# Display_Pics.net
KiCad netlist of a schematic drawn in EAGLE
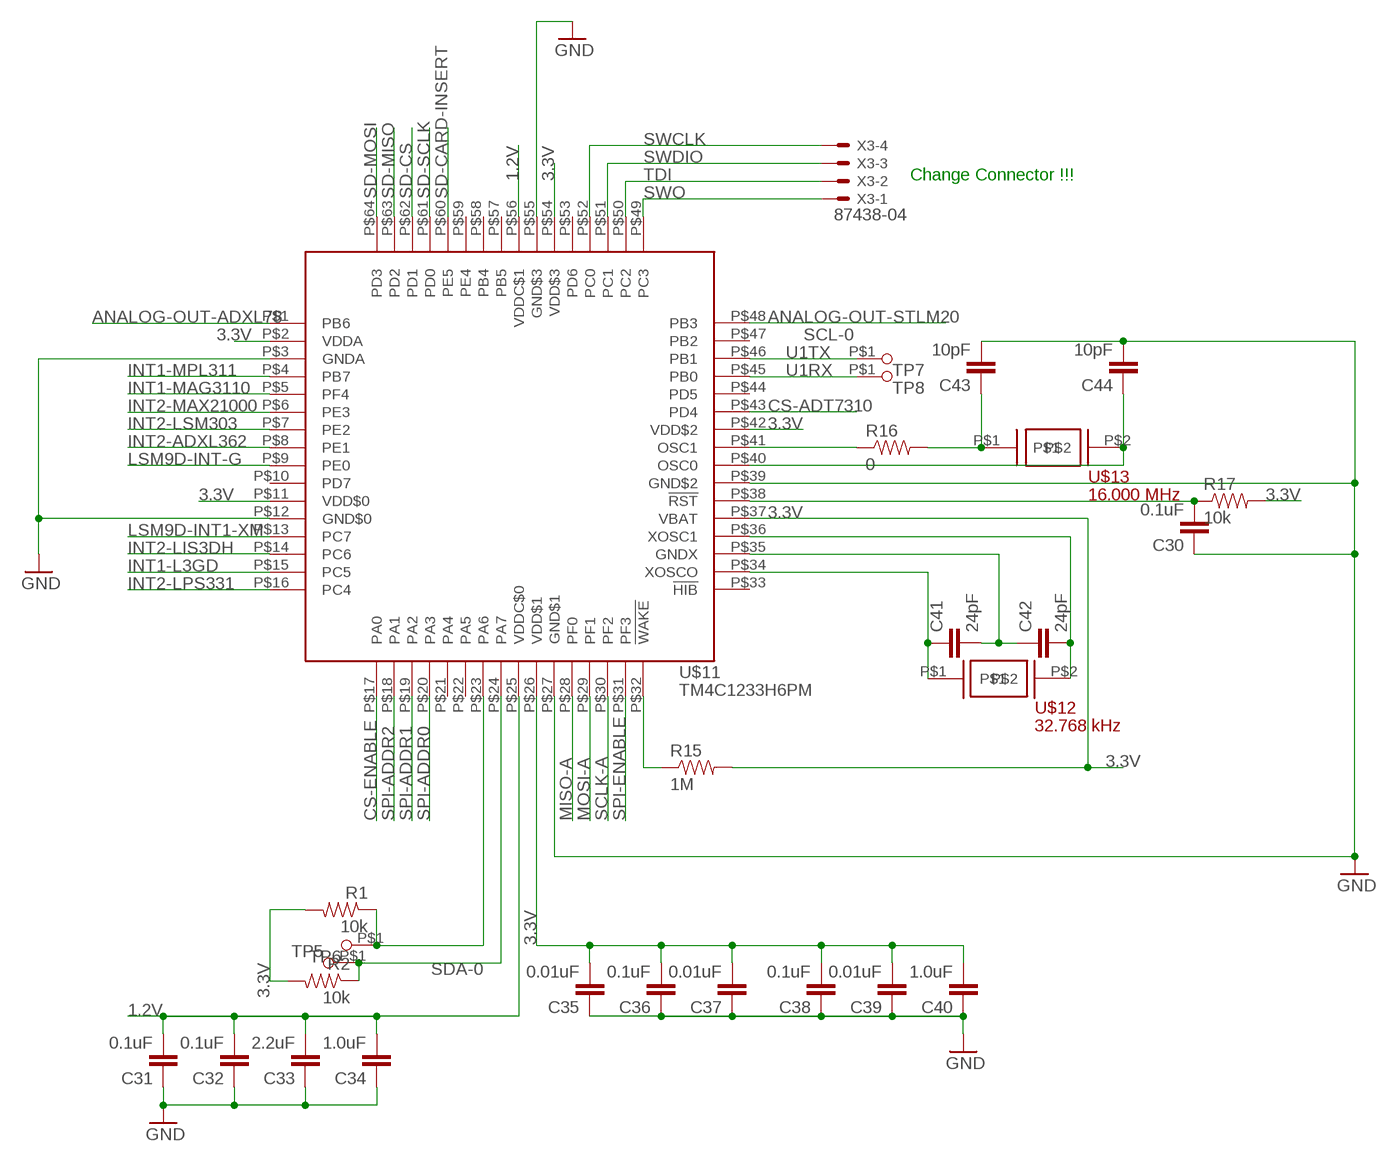
[diagram p0: schematic, sheet 1]
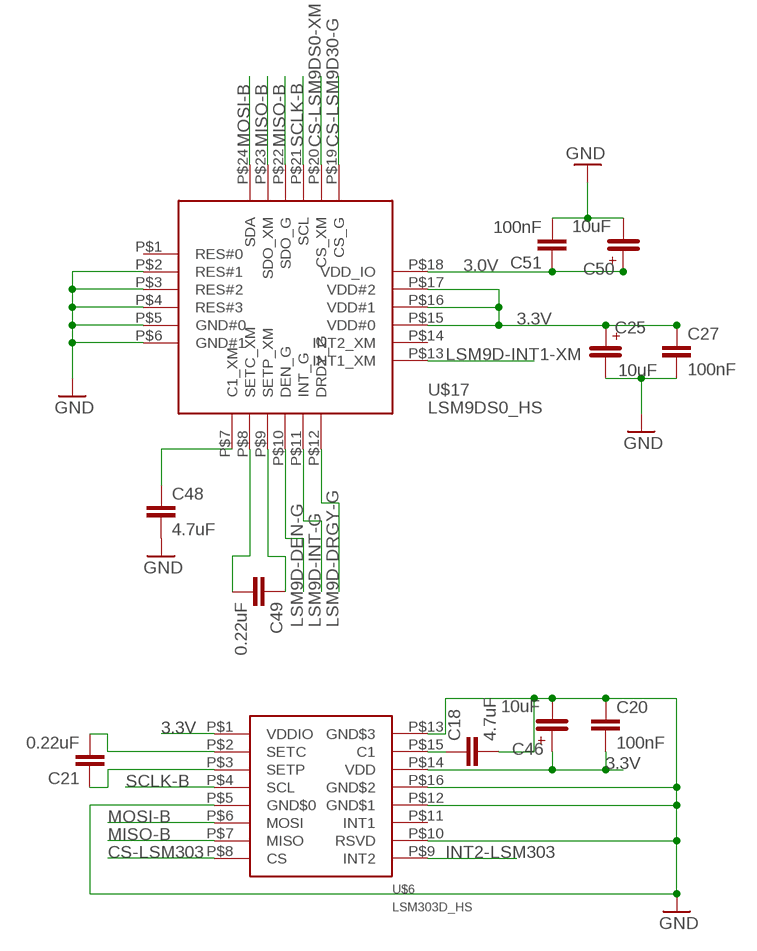
[diagram p1: schematic, sheet 2]
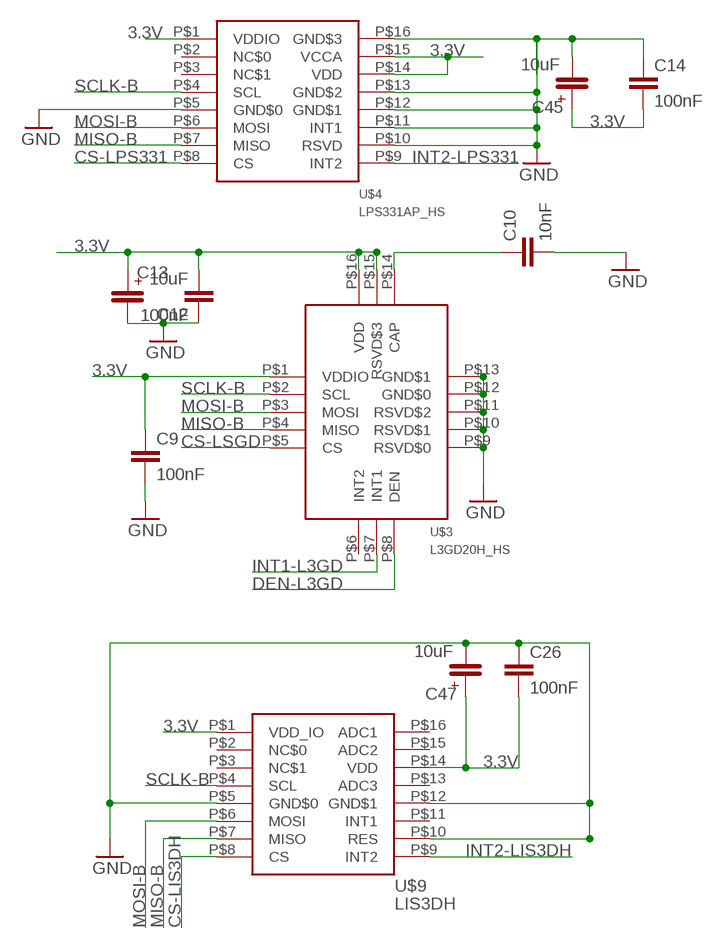
[diagram p2: schematic, sheet 3]
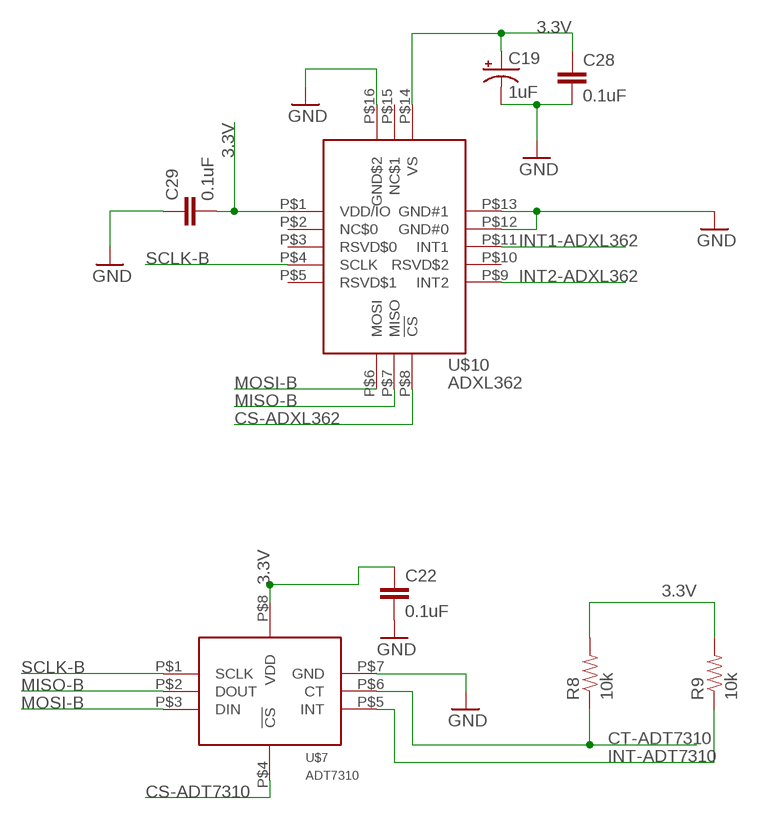
[diagram p3: schematic, sheet 4]
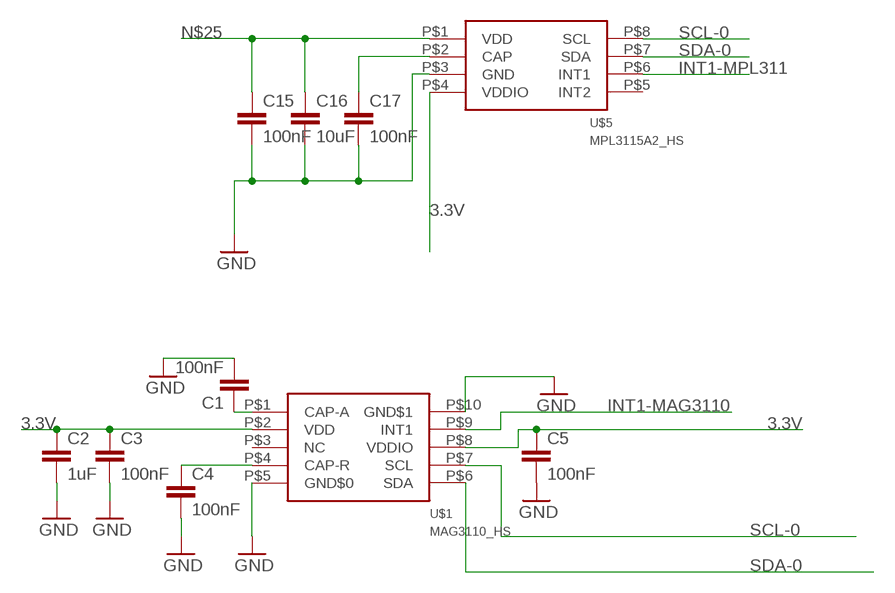
[diagram p4: schematic, sheet 5]
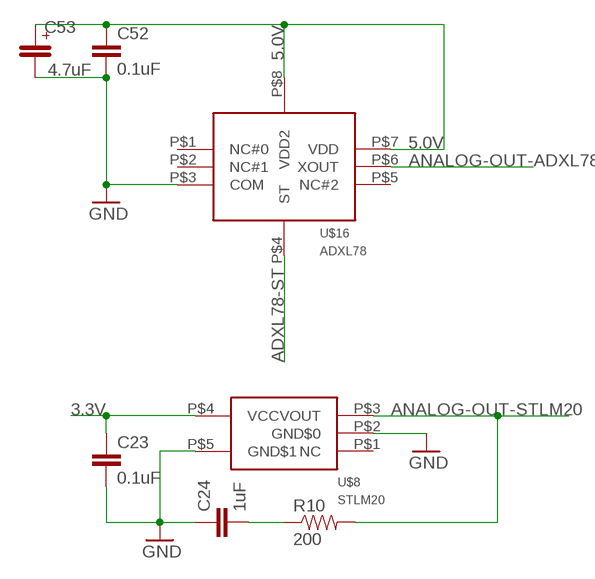
[diagram p5: schematic, sheet 6]
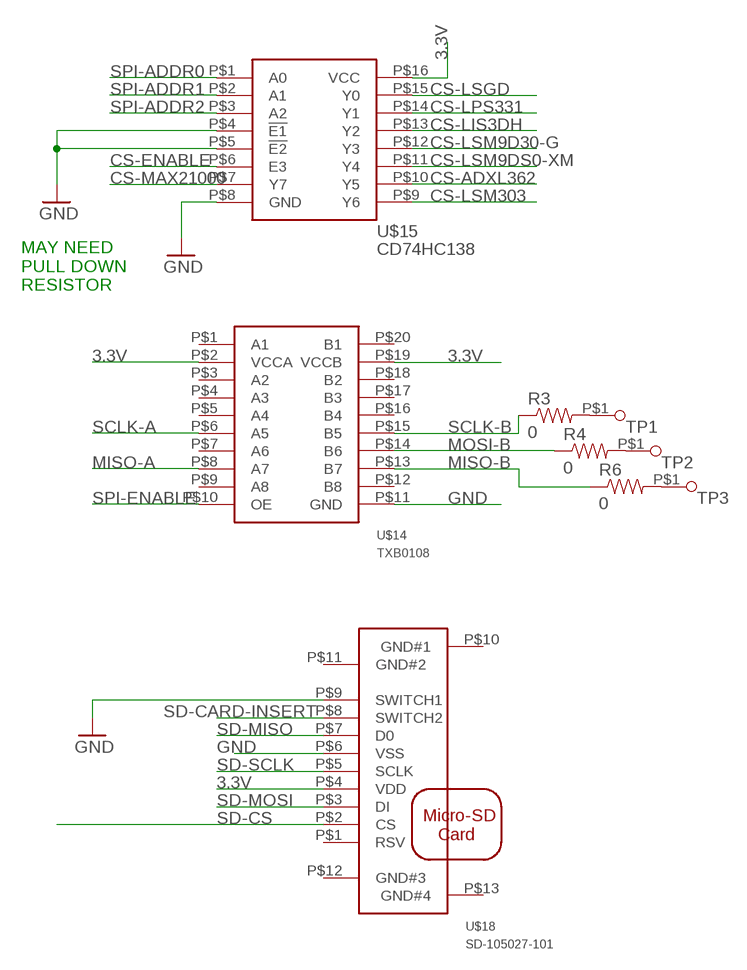
[diagram p6: schematic, sheet 7]
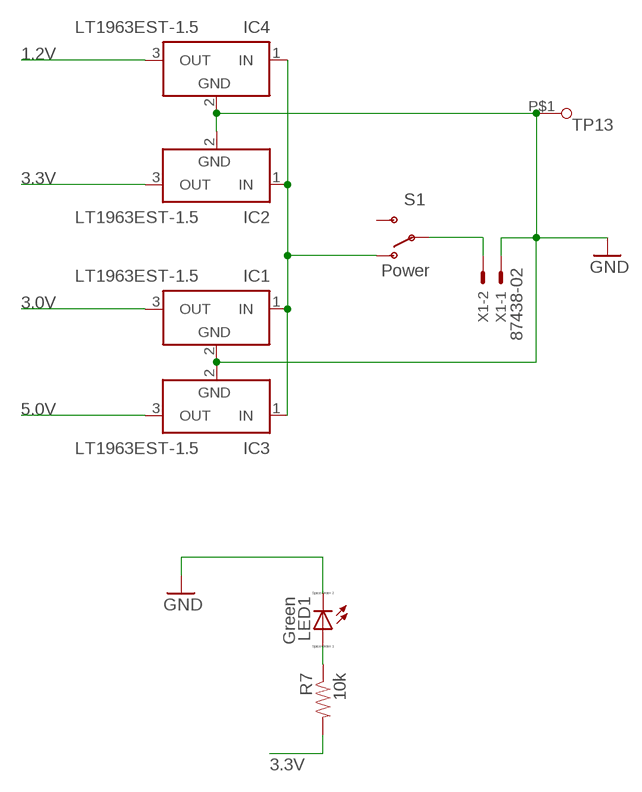
[diagram p7: schematic, sheet 8]
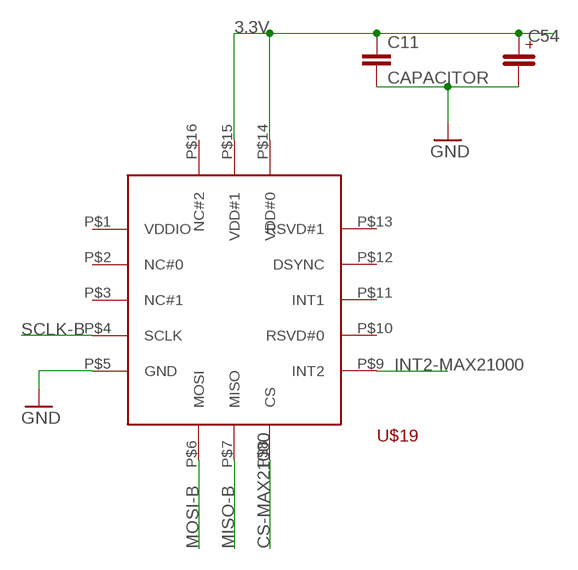
[diagram p8: schematic, sheet 9]

(export (version "E")
  (design (tool "Eeschema 10.0.6"))
  (components
    (comp (ref "C9")
      (value "100nF")
      (footprint "eagle-import:0402-CAP")
      (libsource (lib "eagle-import") (part "CAPACITOR"))
    )
    (comp (ref "C10")
      (value "10nF")
      (footprint "eagle-import:0402-CAP")
      (libsource (lib "eagle-import") (part "CAPACITOR"))
    )
    (comp (ref "C12")
      (value "10uF")
      (footprint "eagle-import:0402-CAP")
      (libsource (lib "eagle-import") (part "CAPACITOR"))
    )
    (comp (ref "C13")
      (value "100nF")
      (footprint "eagle-import:4.3X7.3SMD")
      (libsource (lib "eagle-import") (part "EEFCD0J100ER"))
    )
    (comp (ref "C14")
      (value "100nF")
      (footprint "eagle-import:0402-CAP")
      (libsource (lib "eagle-import") (part "CAPACITOR"))
    )
    (comp (ref "C26")
      (value "100nF")
      (footprint "eagle-import:0402-CAP")
      (libsource (lib "eagle-import") (part "CAPACITOR"))
    )
    (comp (ref "C45")
      (value "10uF")
      (footprint "eagle-import:4.3X7.3SMD")
      (libsource (lib "eagle-import") (part "EEFCD0J100ER"))
    )
    (comp (ref "C47")
      (value "10uF")
      (footprint "eagle-import:4.3X7.3SMD")
      (libsource (lib "eagle-import") (part "EEFCD0J100ER"))
    )
    (comp (ref "U$3")
      (value "L3GD20H_HS")
      (footprint "eagle-import:LGA-16(3X3)_HS")
      (libsource (lib "eagle-import") (part "L3GD20H_HS"))
    )
    (comp (ref "U$4")
      (value "LPS331AP_HS")
      (footprint "eagle-import:LGA-16(3X3)_HS")
      (libsource (lib "eagle-import") (part "LPS331AP_HS"))
    )
    (comp (ref "U$9")
      (value "LIS3DH")
      (footprint "eagle-import:LGA-16(3X3)_HS")
      (libsource (lib "eagle-import") (part "LIS3DH_HS"))
    )
    (comp (ref "C30")
      (value "0.1uF")
      (footprint "eagle-import:0402-CAP")
      (libsource (lib "eagle-import") (part "CAPACITOR"))
    )
    (comp (ref "C31")
      (value "0.1uF")
      (footprint "eagle-import:0402-CAP")
      (libsource (lib "eagle-import") (part "CAPACITOR"))
    )
    (comp (ref "C32")
      (value "0.1uF")
      (footprint "eagle-import:0402-CAP")
      (libsource (lib "eagle-import") (part "CAPACITOR"))
    )
    (comp (ref "C33")
      (value "2.2uF")
      (footprint "eagle-import:0402-CAP")
      (libsource (lib "eagle-import") (part "CAPACITOR"))
    )
    (comp (ref "C34")
      (value "1.0uF")
      (footprint "eagle-import:0402-CAP")
      (libsource (lib "eagle-import") (part "CAPACITOR"))
    )
    (comp (ref "C35")
      (value "0.01uF")
      (footprint "eagle-import:0402-CAP")
      (libsource (lib "eagle-import") (part "CAPACITOR"))
    )
    (comp (ref "C36")
      (value "0.1uF")
      (footprint "eagle-import:0402-CAP")
      (libsource (lib "eagle-import") (part "CAPACITOR"))
    )
    (comp (ref "C37")
      (value "0.01uF")
      (footprint "eagle-import:0402-CAP")
      (libsource (lib "eagle-import") (part "CAPACITOR"))
    )
    (comp (ref "C38")
      (value "0.1uF")
      (footprint "eagle-import:0402-CAP")
      (libsource (lib "eagle-import") (part "CAPACITOR"))
    )
    (comp (ref "C39")
      (value "0.01uF")
      (footprint "eagle-import:0402-CAP")
      (libsource (lib "eagle-import") (part "CAPACITOR"))
    )
    (comp (ref "C40")
      (value "1.0uF")
      (footprint "eagle-import:0402-CAP")
      (libsource (lib "eagle-import") (part "CAPACITOR"))
    )
    (comp (ref "C41")
      (value "24pF")
      (footprint "eagle-import:0402-CAP")
      (libsource (lib "eagle-import") (part "CAPACITOR"))
    )
    (comp (ref "C42")
      (value "24pF")
      (footprint "eagle-import:0402-CAP")
      (libsource (lib "eagle-import") (part "CAPACITOR"))
    )
    (comp (ref "C43")
      (value "10pF")
      (footprint "eagle-import:0402-CAP")
      (libsource (lib "eagle-import") (part "CAPACITOR"))
    )
    (comp (ref "C44")
      (value "10pF")
      (footprint "eagle-import:0402-CAP")
      (libsource (lib "eagle-import") (part "CAPACITOR"))
    )
    (comp (ref "R1")
      (value "10k")
      (footprint "eagle-import:0402-RES")
      (libsource (lib "eagle-import") (part "RESISTOR"))
    )
    (comp (ref "R2")
      (value "10k")
      (footprint "eagle-import:0402-RES")
      (libsource (lib "eagle-import") (part "RESISTOR"))
    )
    (comp (ref "R15")
      (value "1M")
      (footprint "eagle-import:0402-RES")
      (libsource (lib "eagle-import") (part "RESISTOR"))
    )
    (comp (ref "R16")
      (value "0")
      (footprint "eagle-import:0402-RES")
      (libsource (lib "eagle-import") (part "RESISTOR"))
    )
    (comp (ref "R17")
      (value "10k")
      (footprint "eagle-import:0402-RES")
      (libsource (lib "eagle-import") (part "RESISTOR"))
    )
    (comp (ref "TP5")
      (value "TESTPAD(ROUND)")
      (footprint "eagle-import:TESTPAD(ROUND)")
      (libsource (lib "eagle-import") (part "TESTPAD(ROUND)"))
    )
    (comp (ref "TP6")
      (value "TESTPAD(ROUND)")
      (footprint "eagle-import:TESTPAD(ROUND)")
      (libsource (lib "eagle-import") (part "TESTPAD(ROUND)"))
    )
    (comp (ref "TP7")
      (value "TESTPAD(ROUND)")
      (footprint "eagle-import:TESTPAD(ROUND)")
      (libsource (lib "eagle-import") (part "TESTPAD(ROUND)"))
    )
    (comp (ref "TP8")
      (value "TESTPAD(ROUND)")
      (footprint "eagle-import:TESTPAD(ROUND)")
      (libsource (lib "eagle-import") (part "TESTPAD(ROUND)"))
    )
    (comp (ref "U$11")
      (value "TM4C1233H6PM")
      (footprint "eagle-import:S-PQFP-G64")
      (libsource (lib "eagle-import") (part "TM4C1233H6PM"))
    )
    (comp (ref "U$12")
      (value "32.768 kHz")
      (footprint "eagle-import:CYLINDRICAL-(1.9DIAX6L)")
      (libsource (lib "eagle-import") (part "AB26TRB"))
    )
    (comp (ref "U$13")
      (value "16.000 MHz")
      (footprint "eagle-import:2-SMD")
      (libsource (lib "eagle-import") (part "NX5032GA"))
    )
    (comp (ref "X3")
      (value "87438-04")
      (footprint "eagle-import:87438-04")
      (libsource (lib "eagle-import") (part "87438-04"))
    )
    (comp (ref "C18")
      (value "4.7uF")
      (footprint "eagle-import:0402-CAP")
      (libsource (lib "eagle-import") (part "CAPACITOR"))
    )
    (comp (ref "C20")
      (value "100nF")
      (footprint "eagle-import:0402-CAP")
      (libsource (lib "eagle-import") (part "CAPACITOR"))
    )
    (comp (ref "C21")
      (value "0.22uF")
      (footprint "eagle-import:0402-CAP")
      (libsource (lib "eagle-import") (part "CAPACITOR"))
    )
    (comp (ref "C25")
      (value "10uF")
      (footprint "eagle-import:4.3X7.3SMD")
      (libsource (lib "eagle-import") (part "EEFCD0J100ER"))
    )
    (comp (ref "C27")
      (value "100nF")
      (footprint "eagle-import:0402-CAP")
      (libsource (lib "eagle-import") (part "CAPACITOR"))
    )
    (comp (ref "C46")
      (value "10uF")
      (footprint "eagle-import:4.3X7.3SMD")
      (libsource (lib "eagle-import") (part "EEFCD0J100ER"))
    )
    (comp (ref "C48")
      (value "4.7uF")
      (footprint "eagle-import:0402-CAP")
      (libsource (lib "eagle-import") (part "CAPACITOR"))
    )
    (comp (ref "C49")
      (value "0.22uF")
      (footprint "eagle-import:0402-CAP")
      (libsource (lib "eagle-import") (part "CAPACITOR"))
    )
    (comp (ref "C50")
      (value "10uF")
      (footprint "eagle-import:4.3X7.3SMD")
      (libsource (lib "eagle-import") (part "EEFCD0J100ER"))
    )
    (comp (ref "C51")
      (value "100nF")
      (footprint "eagle-import:0402-CAP")
      (libsource (lib "eagle-import") (part "CAPACITOR"))
    )
    (comp (ref "U$6")
      (value "LSM303D_HS")
      (footprint "eagle-import:LGA-16(3X3)_HS")
      (libsource (lib "eagle-import") (part "LSM303D_HS"))
    )
    (comp (ref "U$17")
      (value "LSM9DS0_HS")
      (footprint "eagle-import:LGA-24(4X4)_HS")
      (libsource (lib "eagle-import") (part "LSM9DS0_HS"))
    )
    (comp (ref "C23")
      (value "0.1uF")
      (footprint "eagle-import:0402-CAP")
      (libsource (lib "eagle-import") (part "CAPACITOR"))
    )
    (comp (ref "C24")
      (value "1uF")
      (footprint "eagle-import:0402-CAP")
      (libsource (lib "eagle-import") (part "CAPACITOR"))
    )
    (comp (ref "C52")
      (value "0.1uF")
      (footprint "eagle-import:0402-CAP")
      (libsource (lib "eagle-import") (part "CAPACITOR"))
    )
    (comp (ref "C53")
      (value "4.7uF")
      (footprint "eagle-import:4.3X7.3SMD")
      (libsource (lib "eagle-import") (part "EEFCD0J100ER"))
    )
    (comp (ref "R10")
      (value "200")
      (footprint "eagle-import:0402-RES")
      (libsource (lib "eagle-import") (part "RESISTOR"))
    )
    (comp (ref "U$8")
      (value "STLM20")
      (footprint "eagle-import:SOT323-5L")
      (libsource (lib "eagle-import") (part "STLM20"))
    )
    (comp (ref "U$16")
      (value "ADXL78")
      (footprint "eagle-import:LCC-8(5X5)_HS")
      (libsource (lib "eagle-import") (part "ADXL78"))
    )
    (comp (ref "IC1")
      (value "LT1963EST-1.5")
      (footprint "eagle-import:SOT223")
      (libsource (lib "eagle-import") (part "LT1963EST-1.5"))
    )
    (comp (ref "IC2")
      (value "LT1963EST-1.5")
      (footprint "eagle-import:SOT223")
      (libsource (lib "eagle-import") (part "LT1963EST-1.5"))
    )
    (comp (ref "IC3")
      (value "LT1963EST-1.5")
      (footprint "eagle-import:SOT223")
      (libsource (lib "eagle-import") (part "LT1963EST-1.5"))
    )
    (comp (ref "IC4")
      (value "LT1963EST-1.5")
      (footprint "eagle-import:SOT223")
      (libsource (lib "eagle-import") (part "LT1963EST-1.5"))
    )
    (comp (ref "LED1")
      (value "Green")
      (footprint "eagle-import:LED_SML0603")
      (libsource (lib "eagle-import") (part "LED_ESML0603"))
    )
    (comp (ref "R7")
      (value "10k")
      (footprint "eagle-import:0402-RES")
      (libsource (lib "eagle-import") (part "RESISTOR"))
    )
    (comp (ref "S1")
      (value "Power")
      (footprint "eagle-import:SWITCH-SPST-SMD-A")
      (libsource (lib "eagle-import") (part "SWITCH-SPDT-SMD-A"))
    )
    (comp (ref "TP13")
      (value "TESTPAD(ROUND)")
      (footprint "eagle-import:TESTPAD(ROUND)")
      (libsource (lib "eagle-import") (part "TESTPAD(ROUND)"))
    )
    (comp (ref "X1")
      (value "87438-02")
      (footprint "eagle-import:87438-02")
      (libsource (lib "eagle-import") (part "87438-02"))
    )
    (comp (ref "C1")
      (value "100nF")
      (footprint "eagle-import:0402-CAP")
      (libsource (lib "eagle-import") (part "CAPACITOR"))
    )
    (comp (ref "C2")
      (value "1uF")
      (footprint "eagle-import:0402-CAP")
      (libsource (lib "eagle-import") (part "CAPACITOR"))
    )
    (comp (ref "C3")
      (value "100nF")
      (footprint "eagle-import:0402-CAP")
      (libsource (lib "eagle-import") (part "CAPACITOR"))
    )
    (comp (ref "C4")
      (value "100nF")
      (footprint "eagle-import:0402-CAP")
      (libsource (lib "eagle-import") (part "CAPACITOR"))
    )
    (comp (ref "C5")
      (value "100nF")
      (footprint "eagle-import:0402-CAP")
      (libsource (lib "eagle-import") (part "CAPACITOR"))
    )
    (comp (ref "C15")
      (value "100nF")
      (footprint "eagle-import:0402-CAP")
      (libsource (lib "eagle-import") (part "CAPACITOR"))
    )
    (comp (ref "C16")
      (value "10uF")
      (footprint "eagle-import:0402-CAP")
      (libsource (lib "eagle-import") (part "CAPACITOR"))
    )
    (comp (ref "C17")
      (value "100nF")
      (footprint "eagle-import:0402-CAP")
      (libsource (lib "eagle-import") (part "CAPACITOR"))
    )
    (comp (ref "U$1")
      (value "MAG3110_HS")
      (footprint "eagle-import:DFN-10(2X2)_HS")
      (libsource (lib "eagle-import") (part "MAG3110_HS"))
    )
    (comp (ref "U$5")
      (value "MPL3115A2_HS")
      (footprint "eagle-import:LGA-8(5X3)_HS")
      (libsource (lib "eagle-import") (part "MPL3115A2_HS"))
    )
    (comp (ref "R3")
      (value "0")
      (footprint "eagle-import:0402-RES")
      (libsource (lib "eagle-import") (part "RESISTOR"))
    )
    (comp (ref "R4")
      (value "0")
      (footprint "eagle-import:0402-RES")
      (libsource (lib "eagle-import") (part "RESISTOR"))
    )
    (comp (ref "R6")
      (value "0")
      (footprint "eagle-import:0402-RES")
      (libsource (lib "eagle-import") (part "RESISTOR"))
    )
    (comp (ref "TP1")
      (value "TESTPAD(ROUND)")
      (footprint "eagle-import:TESTPAD(ROUND)")
      (libsource (lib "eagle-import") (part "TESTPAD(ROUND)"))
    )
    (comp (ref "TP2")
      (value "TESTPAD(ROUND)")
      (footprint "eagle-import:TESTPAD(ROUND)")
      (libsource (lib "eagle-import") (part "TESTPAD(ROUND)"))
    )
    (comp (ref "TP3")
      (value "TESTPAD(ROUND)")
      (footprint "eagle-import:TESTPAD(ROUND)")
      (libsource (lib "eagle-import") (part "TESTPAD(ROUND)"))
    )
    (comp (ref "U$14")
      (value "TXB0108")
      (footprint "eagle-import:TSSOP-(PW)-20")
      (libsource (lib "eagle-import") (part "TXB0108"))
    )
    (comp (ref "U$15")
      (value "CD74HC138")
      (footprint "eagle-import:SOIC-16")
      (libsource (lib "eagle-import") (part "CD74HC138"))
    )
    (comp (ref "U$18")
      (value "SD-105027-101")
      (footprint "eagle-import:SD-105027-101")
      (libsource (lib "eagle-import") (part "SD-105027-101"))
    )
    (comp (ref "C19")
      (value "1uF")
      (footprint "eagle-import:EIA6032")
      (libsource (lib "eagle-import") (part "CAP_POL6032"))
    )
    (comp (ref "C22")
      (value "0.1uF")
      (footprint "eagle-import:0402-CAP")
      (libsource (lib "eagle-import") (part "CAPACITOR"))
    )
    (comp (ref "C28")
      (value "0.1uF")
      (footprint "eagle-import:0402-CAP")
      (libsource (lib "eagle-import") (part "CAPACITOR"))
    )
    (comp (ref "C29")
      (value "0.1uF")
      (footprint "eagle-import:0402-CAP")
      (libsource (lib "eagle-import") (part "CAPACITOR"))
    )
    (comp (ref "R8")
      (value "10k")
      (footprint "eagle-import:0402-RES")
      (libsource (lib "eagle-import") (part "RESISTOR"))
    )
    (comp (ref "R9")
      (value "10k")
      (footprint "eagle-import:0402-RES")
      (libsource (lib "eagle-import") (part "RESISTOR"))
    )
    (comp (ref "U$7")
      (value "ADT7310")
      (footprint "eagle-import:SOIC-8(5X6.2)")
      (libsource (lib "eagle-import") (part "ADT7310"))
    )
    (comp (ref "U$10")
      (value "ADXL362")
      (footprint "eagle-import:LGA-16(3X3.25)_HS")
      (libsource (lib "eagle-import") (part "ADXL362_HS"))
    )
    (comp (ref "C11")
      (value "CAPACITOR")
      (footprint "eagle-import:0402-CAP")
      (libsource (lib "eagle-import") (part "CAPACITOR"))
    )
    (comp (ref "C54")
      (value "EEFCD0J100ER")
      (footprint "eagle-import:4.3X7.3SMD")
      (libsource (lib "eagle-import") (part "EEFCD0J100ER"))
    )
    (comp (ref "U$19")
      (value "MAX21000_HS")
      (footprint "eagle-import:LGA-16(3X3)_HS")
      (libsource (lib "eagle-import") (part "MAX21000_HS"))
    )
  )
  (nets
    (net (code "1") (name "1.2V") (class "Default")
      (node (ref "C31") (pin "2") (pinfunction "2_2") (pintype "passive"))
      (node (ref "C32") (pin "2") (pinfunction "2_2") (pintype "passive"))
      (node (ref "C33") (pin "2") (pinfunction "2_2") (pintype "passive"))
      (node (ref "C34") (pin "2") (pinfunction "2_2") (pintype "passive"))
      (node (ref "IC4") (pin "3") (pinfunction "OUT_3") (pintype "output"))
      (node (ref "U$11") (pin "P$25") (pinfunction "VDDC$0_P$25") (pintype "bidirectional"))
      (node (ref "U$11") (pin "P$56") (pinfunction "VDDC$1_P$56") (pintype "bidirectional"))
    )
    (net (code "2") (name "3.0V") (class "Default")
      (node (ref "C50") (pin "P$1") (pintype "bidirectional"))
      (node (ref "C51") (pin "1") (pinfunction "1_1") (pintype "passive"))
      (node (ref "IC1") (pin "3") (pinfunction "OUT_3") (pintype "output"))
      (node (ref "U$17") (pin "P$18") (pinfunction "VDD_IO_P$18") (pintype "bidirectional"))
    )
    (net (code "3") (name "3.3V") (class "Default")
      (node (ref "C11") (pin "1") (pinfunction "1_1") (pintype "passive"))
      (node (ref "C12") (pin "2") (pinfunction "2_2") (pintype "passive"))
      (node (ref "C13") (pin "P$1") (pintype "bidirectional"))
      (node (ref "C14") (pin "2") (pinfunction "2_2") (pintype "passive"))
      (node (ref "C19") (pin "P$1") (pinfunction "+_P$1") (pintype "passive"))
      (node (ref "C2") (pin "1") (pinfunction "1_1") (pintype "passive"))
      (node (ref "C20") (pin "2") (pinfunction "2_2") (pintype "passive"))
      (node (ref "C22") (pin "1") (pinfunction "1_1") (pintype "passive"))
      (node (ref "C23") (pin "1") (pinfunction "1_1") (pintype "passive"))
      (node (ref "C25") (pin "P$1") (pintype "bidirectional"))
      (node (ref "C26") (pin "2") (pinfunction "2_2") (pintype "passive"))
      (node (ref "C27") (pin "1") (pinfunction "1_1") (pintype "passive"))
      (node (ref "C28") (pin "1") (pinfunction "1_1") (pintype "passive"))
      (node (ref "C29") (pin "2") (pinfunction "2_2") (pintype "passive"))
      (node (ref "C3") (pin "1") (pinfunction "1_1") (pintype "passive"))
      (node (ref "C35") (pin "2") (pinfunction "2_2") (pintype "passive"))
      (node (ref "C36") (pin "2") (pinfunction "2_2") (pintype "passive"))
      (node (ref "C37") (pin "2") (pinfunction "2_2") (pintype "passive"))
      (node (ref "C38") (pin "2") (pinfunction "2_2") (pintype "passive"))
      (node (ref "C39") (pin "2") (pinfunction "2_2") (pintype "passive"))
      (node (ref "C40") (pin "2") (pinfunction "2_2") (pintype "passive"))
      (node (ref "C45") (pin "P$1") (pintype "bidirectional"))
      (node (ref "C46") (pin "P$1") (pintype "bidirectional"))
      (node (ref "C47") (pin "P$1") (pintype "bidirectional"))
      (node (ref "C5") (pin "1") (pinfunction "1_1") (pintype "passive"))
      (node (ref "C54") (pin "P$1") (pintype "bidirectional"))
      (node (ref "C9") (pin "1") (pinfunction "1_1") (pintype "passive"))
      (node (ref "IC2") (pin "3") (pinfunction "OUT_3") (pintype "output"))
      (node (ref "R1") (pin "2") (pinfunction "2_2") (pintype "passive"))
      (node (ref "R15") (pin "2") (pinfunction "2_2") (pintype "passive"))
      (node (ref "R17") (pin "2") (pinfunction "2_2") (pintype "passive"))
      (node (ref "R2") (pin "2") (pinfunction "2_2") (pintype "passive"))
      (node (ref "R7") (pin "2") (pinfunction "2_2") (pintype "passive"))
      (node (ref "R8") (pin "2") (pinfunction "2_2") (pintype "passive"))
      (node (ref "R9") (pin "2") (pinfunction "2_2") (pintype "passive"))
      (node (ref "U$1") (pin "P$2") (pinfunction "VDD_P$2") (pintype "bidirectional"))
      (node (ref "U$1") (pin "P$8") (pinfunction "VDDIO_P$8") (pintype "bidirectional"))
      (node (ref "U$10") (pin "P$1") (pinfunction "VDD/IO_P$1") (pintype "bidirectional"))
      (node (ref "U$10") (pin "P$14") (pinfunction "VS_P$14") (pintype "bidirectional"))
      (node (ref "U$11") (pin "P$11") (pinfunction "VDD$0_P$11") (pintype "bidirectional"))
      (node (ref "U$11") (pin "P$2") (pinfunction "VDDA_P$2") (pintype "bidirectional"))
      (node (ref "U$11") (pin "P$26") (pinfunction "VDD$1_P$26") (pintype "bidirectional"))
      (node (ref "U$11") (pin "P$37") (pinfunction "VBAT_P$37") (pintype "bidirectional"))
      (node (ref "U$11") (pin "P$42") (pinfunction "VDD$2_P$42") (pintype "bidirectional"))
      (node (ref "U$11") (pin "P$54") (pinfunction "VDD$3_P$54") (pintype "bidirectional"))
      (node (ref "U$14") (pin "P$19") (pinfunction "VCCB_P$19") (pintype "bidirectional"))
      (node (ref "U$14") (pin "P$2") (pinfunction "VCCA_P$2") (pintype "bidirectional"))
      (node (ref "U$15") (pin "P$16") (pinfunction "VCC_P$16") (pintype "bidirectional"))
      (node (ref "U$17") (pin "P$15") (pinfunction "VDD#0_P$15") (pintype "bidirectional"))
      (node (ref "U$17") (pin "P$16") (pinfunction "VDD#1_P$16") (pintype "bidirectional"))
      (node (ref "U$17") (pin "P$17") (pinfunction "VDD#2_P$17") (pintype "bidirectional"))
      (node (ref "U$18") (pin "P$4") (pinfunction "VDD_P$4") (pintype "bidirectional"))
      (node (ref "U$19") (pin "P$14") (pinfunction "VDD#0_P$14") (pintype "bidirectional"))
      (node (ref "U$19") (pin "P$15") (pinfunction "VDD#1_P$15") (pintype "bidirectional"))
      (node (ref "U$3") (pin "P$1") (pinfunction "VDDIO_P$1") (pintype "bidirectional"))
      (node (ref "U$3") (pin "P$15") (pinfunction "RSVD$3_P$15") (pintype "bidirectional"))
      (node (ref "U$3") (pin "P$16") (pinfunction "VDD_P$16") (pintype "bidirectional"))
      (node (ref "U$4") (pin "P$1") (pinfunction "VDDIO_P$1") (pintype "bidirectional"))
      (node (ref "U$4") (pin "P$14") (pinfunction "VDD_P$14") (pintype "bidirectional"))
      (node (ref "U$4") (pin "P$15") (pinfunction "VCCA_P$15") (pintype "bidirectional"))
      (node (ref "U$5") (pin "P$4") (pinfunction "VDDIO_P$4") (pintype "bidirectional"))
      (node (ref "U$6") (pin "P$1") (pinfunction "VDDIO_P$1") (pintype "bidirectional"))
      (node (ref "U$6") (pin "P$14") (pinfunction "VDD_P$14") (pintype "bidirectional"))
      (node (ref "U$7") (pin "P$8") (pinfunction "VDD_P$8") (pintype "bidirectional"))
      (node (ref "U$8") (pin "P$4") (pinfunction "VCC_P$4") (pintype "bidirectional"))
      (node (ref "U$9") (pin "P$1") (pinfunction "VDD_IO_P$1") (pintype "bidirectional"))
      (node (ref "U$9") (pin "P$14") (pinfunction "VDD_P$14") (pintype "bidirectional"))
    )
    (net (code "4") (name "5.0V") (class "Default")
      (node (ref "C52") (pin "1") (pinfunction "1_1") (pintype "passive"))
      (node (ref "C53") (pin "P$1") (pintype "bidirectional"))
      (node (ref "IC3") (pin "3") (pinfunction "OUT_3") (pintype "output"))
      (node (ref "U$16") (pin "P$7") (pinfunction "VDD_P$7") (pintype "bidirectional"))
      (node (ref "U$16") (pin "P$8") (pinfunction "VDD2_P$8") (pintype "bidirectional"))
    )
    (net (code "5") (name "ADXL78-ST") (class "Default")
      (node (ref "U$16") (pin "P$4") (pinfunction "ST_P$4") (pintype "bidirectional"))
    )
    (net (code "6") (name "ANALOG-OUT-ADXL78") (class "Default")
      (node (ref "U$11") (pin "P$1") (pinfunction "PB6_P$1") (pintype "bidirectional"))
      (node (ref "U$16") (pin "P$6") (pinfunction "XOUT_P$6") (pintype "bidirectional"))
    )
    (net (code "7") (name "ANALOG-OUT-STLM20") (class "Default")
      (node (ref "R10") (pin "2") (pinfunction "2_2") (pintype "passive"))
      (node (ref "U$11") (pin "P$48") (pinfunction "PB3_P$48") (pintype "bidirectional"))
      (node (ref "U$8") (pin "P$3") (pinfunction "VOUT_P$3") (pintype "bidirectional"))
    )
    (net (code "8") (name "CS-ADT7310") (class "Default")
      (node (ref "U$11") (pin "P$43") (pinfunction "PD4_P$43") (pintype "bidirectional"))
      (node (ref "U$7") (pin "P$4") (pinfunction "~{CS}_P$4") (pintype "bidirectional"))
    )
    (net (code "9") (name "CS-ADXL362") (class "Default")
      (node (ref "U$10") (pin "P$8") (pinfunction "~{CS}_P$8") (pintype "bidirectional"))
      (node (ref "U$15") (pin "P$10") (pinfunction "Y5_P$10") (pintype "bidirectional"))
    )
    (net (code "10") (name "CS-ENABLE") (class "Default")
      (node (ref "U$11") (pin "P$17") (pinfunction "PA0_P$17") (pintype "bidirectional"))
      (node (ref "U$15") (pin "P$6") (pinfunction "E3_P$6") (pintype "bidirectional"))
    )
    (net (code "11") (name "CS-LIS3DH") (class "Default")
      (node (ref "U$15") (pin "P$13") (pinfunction "Y2_P$13") (pintype "bidirectional"))
      (node (ref "U$9") (pin "P$8") (pinfunction "CS_P$8") (pintype "bidirectional"))
    )
    (net (code "12") (name "CS-LPS331") (class "Default")
      (node (ref "U$15") (pin "P$14") (pinfunction "Y1_P$14") (pintype "bidirectional"))
      (node (ref "U$4") (pin "P$8") (pinfunction "CS_P$8") (pintype "bidirectional"))
    )
    (net (code "13") (name "CS-LSGD") (class "Default")
      (node (ref "U$15") (pin "P$15") (pinfunction "Y0_P$15") (pintype "bidirectional"))
      (node (ref "U$3") (pin "P$5") (pinfunction "CS_P$5") (pintype "bidirectional"))
    )
    (net (code "14") (name "CS-LSM9D30-G") (class "Default")
      (node (ref "U$15") (pin "P$12") (pinfunction "Y3_P$12") (pintype "bidirectional"))
      (node (ref "U$17") (pin "P$19") (pinfunction "CS_G_P$19") (pintype "bidirectional"))
    )
    (net (code "15") (name "CS-LSM9DS0-XM") (class "Default")
      (node (ref "U$15") (pin "P$11") (pinfunction "Y4_P$11") (pintype "bidirectional"))
      (node (ref "U$17") (pin "P$20") (pinfunction "CS_XM_P$20") (pintype "bidirectional"))
    )
    (net (code "16") (name "CS-LSM303") (class "Default")
      (node (ref "U$15") (pin "P$9") (pinfunction "Y6_P$9") (pintype "bidirectional"))
      (node (ref "U$6") (pin "P$8") (pinfunction "CS_P$8") (pintype "bidirectional"))
    )
    (net (code "17") (name "CS-MAX21000") (class "Default")
      (node (ref "U$15") (pin "P$7") (pinfunction "Y7_P$7") (pintype "bidirectional"))
      (node (ref "U$19") (pin "P$8") (pinfunction "CS_P$8") (pintype "bidirectional"))
    )
    (net (code "18") (name "CT-ADT7310") (class "Default")
      (node (ref "R8") (pin "1") (pinfunction "1_1") (pintype "passive"))
      (node (ref "U$7") (pin "P$6") (pinfunction "CT_P$6") (pintype "bidirectional"))
    )
    (net (code "19") (name "DEN-L3GD") (class "Default")
      (node (ref "U$3") (pin "P$8") (pinfunction "DEN_P$8") (pintype "bidirectional"))
    )
    (net (code "20") (name "GND") (class "Default")
      (node (ref "C1") (pin "2") (pinfunction "2_2") (pintype "passive"))
      (node (ref "C10") (pin "2") (pinfunction "2_2") (pintype "passive"))
      (node (ref "C11") (pin "2") (pinfunction "2_2") (pintype "passive"))
      (node (ref "C12") (pin "1") (pinfunction "1_1") (pintype "passive"))
      (node (ref "C13") (pin "P$2") (pintype "bidirectional"))
      (node (ref "C14") (pin "1") (pinfunction "1_1") (pintype "passive"))
      (node (ref "C15") (pin "2") (pinfunction "2_2") (pintype "passive"))
      (node (ref "C16") (pin "2") (pinfunction "2_2") (pintype "passive"))
      (node (ref "C17") (pin "2") (pinfunction "2_2") (pintype "passive"))
      (node (ref "C18") (pin "2") (pinfunction "2_2") (pintype "passive"))
      (node (ref "C19") (pin "P$2") (pinfunction "-_P$2") (pintype "passive"))
      (node (ref "C2") (pin "2") (pinfunction "2_2") (pintype "passive"))
      (node (ref "C20") (pin "1") (pinfunction "1_1") (pintype "passive"))
      (node (ref "C22") (pin "2") (pinfunction "2_2") (pintype "passive"))
      (node (ref "C23") (pin "2") (pinfunction "2_2") (pintype "passive"))
      (node (ref "C24") (pin "1") (pinfunction "1_1") (pintype "passive"))
      (node (ref "C25") (pin "P$2") (pintype "bidirectional"))
      (node (ref "C26") (pin "1") (pinfunction "1_1") (pintype "passive"))
      (node (ref "C27") (pin "2") (pinfunction "2_2") (pintype "passive"))
      (node (ref "C28") (pin "2") (pinfunction "2_2") (pintype "passive"))
      (node (ref "C29") (pin "1") (pinfunction "1_1") (pintype "passive"))
      (node (ref "C3") (pin "2") (pinfunction "2_2") (pintype "passive"))
      (node (ref "C30") (pin "1") (pinfunction "1_1") (pintype "passive"))
      (node (ref "C31") (pin "1") (pinfunction "1_1") (pintype "passive"))
      (node (ref "C32") (pin "1") (pinfunction "1_1") (pintype "passive"))
      (node (ref "C33") (pin "1") (pinfunction "1_1") (pintype "passive"))
      (node (ref "C34") (pin "1") (pinfunction "1_1") (pintype "passive"))
      (node (ref "C35") (pin "1") (pinfunction "1_1") (pintype "passive"))
      (node (ref "C36") (pin "1") (pinfunction "1_1") (pintype "passive"))
      (node (ref "C37") (pin "1") (pinfunction "1_1") (pintype "passive"))
      (node (ref "C38") (pin "1") (pinfunction "1_1") (pintype "passive"))
      (node (ref "C39") (pin "1") (pinfunction "1_1") (pintype "passive"))
      (node (ref "C4") (pin "2") (pinfunction "2_2") (pintype "passive"))
      (node (ref "C40") (pin "1") (pinfunction "1_1") (pintype "passive"))
      (node (ref "C43") (pin "2") (pinfunction "2_2") (pintype "passive"))
      (node (ref "C44") (pin "2") (pinfunction "2_2") (pintype "passive"))
      (node (ref "C45") (pin "P$2") (pintype "bidirectional"))
      (node (ref "C46") (pin "P$2") (pintype "bidirectional"))
      (node (ref "C47") (pin "P$2") (pintype "bidirectional"))
      (node (ref "C48") (pin "2") (pinfunction "2_2") (pintype "passive"))
      (node (ref "C5") (pin "2") (pinfunction "2_2") (pintype "passive"))
      (node (ref "C50") (pin "P$2") (pintype "bidirectional"))
      (node (ref "C51") (pin "2") (pinfunction "2_2") (pintype "passive"))
      (node (ref "C52") (pin "2") (pinfunction "2_2") (pintype "passive"))
      (node (ref "C53") (pin "P$2") (pintype "bidirectional"))
      (node (ref "C54") (pin "P$2") (pintype "bidirectional"))
      (node (ref "C9") (pin "2") (pinfunction "2_2") (pintype "passive"))
      (node (ref "IC1") (pin "2") (pinfunction "GND_2") (pintype "power_in"))
      (node (ref "IC2") (pin "2") (pinfunction "GND_2") (pintype "power_in"))
      (node (ref "IC3") (pin "2") (pinfunction "GND_2") (pintype "power_in"))
      (node (ref "IC4") (pin "2") (pinfunction "GND_2") (pintype "power_in"))
      (node (ref "LED1") (pin "C") (pinfunction "C_C") (pintype "passive"))
      (node (ref "TP13") (pin "P$1") (pinfunction "P$1_P$1") (pintype "bidirectional"))
      (node (ref "U$1") (pin "P$10") (pinfunction "GND$1_P$10") (pintype "bidirectional"))
      (node (ref "U$1") (pin "P$5") (pinfunction "GND$0_P$5") (pintype "bidirectional"))
      (node (ref "U$10") (pin "P$12") (pinfunction "GND#0_P$12") (pintype "bidirectional"))
      (node (ref "U$10") (pin "P$13") (pinfunction "GND#1_P$13") (pintype "bidirectional"))
      (node (ref "U$10") (pin "P$16") (pinfunction "GND$2_P$16") (pintype "bidirectional"))
      (node (ref "U$11") (pin "P$12") (pinfunction "GND$0_P$12") (pintype "bidirectional"))
      (node (ref "U$11") (pin "P$27") (pinfunction "GND$1_P$27") (pintype "bidirectional"))
      (node (ref "U$11") (pin "P$3") (pinfunction "GNDA_P$3") (pintype "bidirectional"))
      (node (ref "U$11") (pin "P$39") (pinfunction "GND$2_P$39") (pintype "bidirectional"))
      (node (ref "U$11") (pin "P$55") (pinfunction "GND$3_P$55") (pintype "bidirectional"))
      (node (ref "U$14") (pin "P$11") (pinfunction "GND_P$11") (pintype "bidirectional"))
      (node (ref "U$15") (pin "P$4") (pinfunction "~{E1}_P$4") (pintype "bidirectional"))
      (node (ref "U$15") (pin "P$5") (pinfunction "~{E2}_P$5") (pintype "bidirectional"))
      (node (ref "U$15") (pin "P$8") (pinfunction "GND_P$8") (pintype "bidirectional"))
      (node (ref "U$16") (pin "P$3") (pinfunction "COM_P$3") (pintype "bidirectional"))
      (node (ref "U$17") (pin "P$2") (pinfunction "RES#1_P$2") (pintype "bidirectional"))
      (node (ref "U$17") (pin "P$3") (pinfunction "RES#2_P$3") (pintype "bidirectional"))
      (node (ref "U$17") (pin "P$4") (pinfunction "RES#3_P$4") (pintype "bidirectional"))
      (node (ref "U$17") (pin "P$5") (pinfunction "GND#0_P$5") (pintype "bidirectional"))
      (node (ref "U$17") (pin "P$6") (pinfunction "GND#1_P$6") (pintype "bidirectional"))
      (node (ref "U$18") (pin "P$6") (pinfunction "VSS_P$6") (pintype "bidirectional"))
      (node (ref "U$18") (pin "P$9") (pinfunction "SWITCH1_P$9") (pintype "bidirectional"))
      (node (ref "U$19") (pin "P$5") (pinfunction "GND_P$5") (pintype "bidirectional"))
      (node (ref "U$3") (pin "P$10") (pinfunction "RSVD$1_P$10") (pintype "bidirectional"))
      (node (ref "U$3") (pin "P$11") (pinfunction "RSVD$2_P$11") (pintype "bidirectional"))
      (node (ref "U$3") (pin "P$12") (pinfunction "GND$0_P$12") (pintype "bidirectional"))
      (node (ref "U$3") (pin "P$13") (pinfunction "GND$1_P$13") (pintype "bidirectional"))
      (node (ref "U$3") (pin "P$9") (pinfunction "RSVD$0_P$9") (pintype "bidirectional"))
      (node (ref "U$4") (pin "P$10") (pinfunction "RSVD_P$10") (pintype "bidirectional"))
      (node (ref "U$4") (pin "P$11") (pinfunction "INT1_P$11") (pintype "bidirectional"))
      (node (ref "U$4") (pin "P$12") (pinfunction "GND$1_P$12") (pintype "bidirectional"))
      (node (ref "U$4") (pin "P$13") (pinfunction "GND$2_P$13") (pintype "bidirectional"))
      (node (ref "U$4") (pin "P$16") (pinfunction "GND$3_P$16") (pintype "bidirectional"))
      (node (ref "U$4") (pin "P$5") (pinfunction "GND$0_P$5") (pintype "bidirectional"))
      (node (ref "U$5") (pin "P$3") (pinfunction "GND_P$3") (pintype "bidirectional"))
      (node (ref "U$6") (pin "P$10") (pinfunction "RSVD_P$10") (pintype "bidirectional"))
      (node (ref "U$6") (pin "P$12") (pinfunction "GND$1_P$12") (pintype "bidirectional"))
      (node (ref "U$6") (pin "P$13") (pinfunction "GND$3_P$13") (pintype "bidirectional"))
      (node (ref "U$6") (pin "P$16") (pinfunction "GND$2_P$16") (pintype "bidirectional"))
      (node (ref "U$6") (pin "P$5") (pinfunction "GND$0_P$5") (pintype "bidirectional"))
      (node (ref "U$7") (pin "P$7") (pinfunction "GND_P$7") (pintype "bidirectional"))
      (node (ref "U$8") (pin "P$2") (pinfunction "GND$0_P$2") (pintype "bidirectional"))
      (node (ref "U$8") (pin "P$5") (pinfunction "GND$1_P$5") (pintype "bidirectional"))
      (node (ref "U$9") (pin "P$10") (pinfunction "RES_P$10") (pintype "bidirectional"))
      (node (ref "U$9") (pin "P$12") (pinfunction "GND$1_P$12") (pintype "bidirectional"))
      (node (ref "U$9") (pin "P$5") (pinfunction "GND$0_P$5") (pintype "bidirectional"))
      (node (ref "X1") (pin "1") (pinfunction "S_1") (pintype "passive"))
    )
    (net (code "21") (name "INT-ADT7310") (class "Default")
      (node (ref "R9") (pin "1") (pinfunction "1_1") (pintype "passive"))
      (node (ref "U$7") (pin "P$5") (pinfunction "INT_P$5") (pintype "bidirectional"))
    )
    (net (code "22") (name "INT1-ADXL362") (class "Default")
      (node (ref "U$10") (pin "P$11") (pinfunction "INT1_P$11") (pintype "bidirectional"))
    )
    (net (code "23") (name "INT1-L3GD") (class "Default")
      (node (ref "U$11") (pin "P$15") (pinfunction "PC5_P$15") (pintype "bidirectional"))
      (node (ref "U$3") (pin "P$7") (pinfunction "INT1_P$7") (pintype "bidirectional"))
    )
    (net (code "24") (name "INT1-MAG3110") (class "Default")
      (node (ref "U$1") (pin "P$9") (pinfunction "INT1_P$9") (pintype "bidirectional"))
      (node (ref "U$11") (pin "P$5") (pinfunction "PF4_P$5") (pintype "bidirectional"))
    )
    (net (code "25") (name "INT1-MPL311") (class "Default")
      (node (ref "U$11") (pin "P$4") (pinfunction "PB7_P$4") (pintype "bidirectional"))
      (node (ref "U$5") (pin "P$6") (pinfunction "INT1_P$6") (pintype "bidirectional"))
    )
    (net (code "26") (name "INT2-ADXL362") (class "Default")
      (node (ref "U$10") (pin "P$9") (pinfunction "INT2_P$9") (pintype "bidirectional"))
      (node (ref "U$11") (pin "P$8") (pinfunction "PE1_P$8") (pintype "bidirectional"))
    )
    (net (code "27") (name "INT2-LIS3DH") (class "Default")
      (node (ref "U$11") (pin "P$14") (pinfunction "PC6_P$14") (pintype "bidirectional"))
      (node (ref "U$9") (pin "P$9") (pinfunction "INT2_P$9") (pintype "bidirectional"))
    )
    (net (code "28") (name "INT2-LPS331") (class "Default")
      (node (ref "U$11") (pin "P$16") (pinfunction "PC4_P$16") (pintype "bidirectional"))
      (node (ref "U$4") (pin "P$9") (pinfunction "INT2_P$9") (pintype "bidirectional"))
    )
    (net (code "29") (name "INT2-LSM303") (class "Default")
      (node (ref "U$11") (pin "P$7") (pinfunction "PE2_P$7") (pintype "bidirectional"))
      (node (ref "U$6") (pin "P$9") (pinfunction "INT2_P$9") (pintype "bidirectional"))
    )
    (net (code "30") (name "INT2-MAX21000") (class "Default")
      (node (ref "U$11") (pin "P$6") (pinfunction "PE3_P$6") (pintype "bidirectional"))
      (node (ref "U$19") (pin "P$9") (pinfunction "INT2_P$9") (pintype "bidirectional"))
    )
    (net (code "31") (name "LSM9D-DEN-G") (class "Default")
      (node (ref "U$17") (pin "P$10") (pinfunction "DEN_G_P$10") (pintype "bidirectional"))
    )
    (net (code "32") (name "LSM9D-DRGY-G") (class "Default")
      (node (ref "U$17") (pin "P$12") (pinfunction "DRDY_G_P$12") (pintype "bidirectional"))
    )
    (net (code "33") (name "LSM9D-INT-G") (class "Default")
      (node (ref "U$11") (pin "P$9") (pinfunction "PE0_P$9") (pintype "bidirectional"))
      (node (ref "U$17") (pin "P$11") (pinfunction "INT_G_P$11") (pintype "bidirectional"))
    )
    (net (code "34") (name "LSM9D-INT1-XM") (class "Default")
      (node (ref "U$11") (pin "P$13") (pinfunction "PC7_P$13") (pintype "bidirectional"))
      (node (ref "U$17") (pin "P$13") (pinfunction "INT1_XM_P$13") (pintype "bidirectional"))
    )
    (net (code "35") (name "MISO-A") (class "Default")
      (node (ref "U$11") (pin "P$28") (pinfunction "PF0_P$28") (pintype "bidirectional"))
      (node (ref "U$14") (pin "P$8") (pinfunction "A7_P$8") (pintype "bidirectional"))
    )
    (net (code "36") (name "MISO-B") (class "Default")
      (node (ref "R6") (pin "1") (pinfunction "1_1") (pintype "passive"))
      (node (ref "U$10") (pin "P$7") (pinfunction "MISO_P$7") (pintype "bidirectional"))
      (node (ref "U$14") (pin "P$13") (pinfunction "B7_P$13") (pintype "bidirectional"))
      (node (ref "U$17") (pin "P$22") (pinfunction "SDO_G_P$22") (pintype "bidirectional"))
      (node (ref "U$17") (pin "P$23") (pinfunction "SDO_XM_P$23") (pintype "bidirectional"))
      (node (ref "U$19") (pin "P$7") (pinfunction "MISO_P$7") (pintype "bidirectional"))
      (node (ref "U$3") (pin "P$4") (pinfunction "MISO_P$4") (pintype "bidirectional"))
      (node (ref "U$4") (pin "P$7") (pinfunction "MISO_P$7") (pintype "bidirectional"))
      (node (ref "U$6") (pin "P$7") (pinfunction "MISO_P$7") (pintype "bidirectional"))
      (node (ref "U$7") (pin "P$2") (pinfunction "DOUT_P$2") (pintype "bidirectional"))
      (node (ref "U$9") (pin "P$7") (pinfunction "MISO_P$7") (pintype "bidirectional"))
    )
    (net (code "37") (name "MOSI-A") (class "Default")
      (node (ref "U$11") (pin "P$29") (pinfunction "PF1_P$29") (pintype "bidirectional"))
    )
    (net (code "38") (name "MOSI-B") (class "Default")
      (node (ref "R4") (pin "1") (pinfunction "1_1") (pintype "passive"))
      (node (ref "U$10") (pin "P$6") (pinfunction "MOSI_P$6") (pintype "bidirectional"))
      (node (ref "U$14") (pin "P$14") (pinfunction "B6_P$14") (pintype "bidirectional"))
      (node (ref "U$17") (pin "P$24") (pinfunction "SDA_P$24") (pintype "bidirectional"))
      (node (ref "U$19") (pin "P$6") (pinfunction "MOSI_P$6") (pintype "bidirectional"))
      (node (ref "U$3") (pin "P$3") (pinfunction "MOSI_P$3") (pintype "bidirectional"))
      (node (ref "U$4") (pin "P$6") (pinfunction "MOSI_P$6") (pintype "bidirectional"))
      (node (ref "U$6") (pin "P$6") (pinfunction "MOSI_P$6") (pintype "bidirectional"))
      (node (ref "U$7") (pin "P$3") (pinfunction "DIN_P$3") (pintype "bidirectional"))
      (node (ref "U$9") (pin "P$6") (pinfunction "MOSI_P$6") (pintype "bidirectional"))
    )
    (net (code "39") (name "N$25") (class "Default")
      (node (ref "C15") (pin "1") (pinfunction "1_1") (pintype "passive"))
      (node (ref "C16") (pin "1") (pinfunction "1_1") (pintype "passive"))
      (node (ref "U$5") (pin "P$1") (pinfunction "VDD_P$1") (pintype "bidirectional"))
    )
    (net (code "40") (name "Net-(C24-Pad2)") (class "Default")
      (node (ref "C24") (pin "2") (pinfunction "2_2") (pintype "passive"))
      (node (ref "R10") (pin "1") (pinfunction "1_1") (pintype "passive"))
    )
    (net (code "41") (name "Net-(C43-Pad1)") (class "Default")
      (node (ref "C43") (pin "1") (pinfunction "1_1") (pintype "passive"))
      (node (ref "R16") (pin "2") (pinfunction "2_2") (pintype "passive"))
      (node (ref "U$13") (pin "P$1") (pinfunction "P$1_P$1") (pintype "bidirectional"))
    )
    (net (code "42") (name "Net-(IC1A-IN)") (class "Default")
      (node (ref "IC1") (pin "1") (pinfunction "IN_1") (pintype "input"))
      (node (ref "IC2") (pin "1") (pinfunction "IN_1") (pintype "input"))
      (node (ref "IC3") (pin "1") (pinfunction "IN_1") (pintype "input"))
      (node (ref "IC4") (pin "1") (pinfunction "IN_1") (pintype "input"))
      (node (ref "S1") (pin "1") (pinfunction "O_1") (pintype "passive"))
    )
    (net (code "43") (name "Net-(LED1-PadA)") (class "Default")
      (node (ref "LED1") (pin "A") (pinfunction "A_A") (pintype "passive"))
      (node (ref "R7") (pin "1") (pinfunction "1_1") (pintype "passive"))
    )
    (net (code "44") (name "Net-(R3-Pad2)") (class "Default")
      (node (ref "R3") (pin "2") (pinfunction "2_2") (pintype "passive"))
      (node (ref "TP1") (pin "P$1") (pinfunction "P$1_P$1") (pintype "bidirectional"))
    )
    (net (code "45") (name "Net-(R4-Pad2)") (class "Default")
      (node (ref "R4") (pin "2") (pinfunction "2_2") (pintype "passive"))
      (node (ref "TP2") (pin "P$1") (pinfunction "P$1_P$1") (pintype "bidirectional"))
    )
    (net (code "46") (name "Net-(R6-Pad2)") (class "Default")
      (node (ref "R6") (pin "2") (pinfunction "2_2") (pintype "passive"))
      (node (ref "TP3") (pin "P$1") (pinfunction "P$1_P$1") (pintype "bidirectional"))
    )
    (net (code "47") (name "Net-(S1-P)") (class "Default")
      (node (ref "S1") (pin "2") (pinfunction "P_2") (pintype "passive"))
      (node (ref "X1") (pin "2") (pinfunction "S_2") (pintype "passive"))
    )
    (net (code "48") (name "Net-(U$1-CAP-A)") (class "Default")
      (node (ref "C1") (pin "1") (pinfunction "1_1") (pintype "passive"))
      (node (ref "U$1") (pin "P$1") (pinfunction "CAP-A_P$1") (pintype "bidirectional"))
    )
    (net (code "49") (name "Net-(U$1-CAP-R)") (class "Default")
      (node (ref "C4") (pin "1") (pinfunction "1_1") (pintype "passive"))
      (node (ref "U$1") (pin "P$4") (pinfunction "CAP-R_P$4") (pintype "bidirectional"))
    )
    (net (code "50") (name "Net-(U$3-CAP)") (class "Default")
      (node (ref "C10") (pin "1") (pinfunction "1_1") (pintype "passive"))
      (node (ref "U$3") (pin "P$14") (pinfunction "CAP_P$14") (pintype "bidirectional"))
    )
    (net (code "51") (name "Net-(U$5-CAP)") (class "Default")
      (node (ref "C17") (pin "1") (pinfunction "1_1") (pintype "passive"))
      (node (ref "U$5") (pin "P$2") (pinfunction "CAP_P$2") (pintype "bidirectional"))
    )
    (net (code "52") (name "Net-(U$6-C1)") (class "Default")
      (node (ref "C18") (pin "1") (pinfunction "1_1") (pintype "passive"))
      (node (ref "U$6") (pin "P$15") (pinfunction "C1_P$15") (pintype "bidirectional"))
    )
    (net (code "53") (name "Net-(U$6-SETC)") (class "Default")
      (node (ref "C21") (pin "2") (pinfunction "2_2") (pintype "passive"))
      (node (ref "U$6") (pin "P$2") (pinfunction "SETC_P$2") (pintype "bidirectional"))
    )
    (net (code "54") (name "Net-(U$6-SETP)") (class "Default")
      (node (ref "C21") (pin "1") (pinfunction "1_1") (pintype "passive"))
      (node (ref "U$6") (pin "P$3") (pinfunction "SETP_P$3") (pintype "bidirectional"))
    )
    (net (code "55") (name "Net-(U$11-GNDX)") (class "Default")
      (node (ref "C41") (pin "2") (pinfunction "2_2") (pintype "passive"))
      (node (ref "C42") (pin "1") (pinfunction "1_1") (pintype "passive"))
      (node (ref "U$11") (pin "P$35") (pinfunction "GNDX_P$35") (pintype "bidirectional"))
    )
    (net (code "56") (name "Net-(U$11-OSC0)") (class "Default")
      (node (ref "C44") (pin "1") (pinfunction "1_1") (pintype "passive"))
      (node (ref "U$11") (pin "P$40") (pinfunction "OSC0_P$40") (pintype "bidirectional"))
      (node (ref "U$13") (pin "P$2") (pinfunction "P$2_P$2") (pintype "bidirectional"))
    )
    (net (code "57") (name "Net-(U$11-OSC1)") (class "Default")
      (node (ref "R16") (pin "1") (pinfunction "1_1") (pintype "passive"))
      (node (ref "U$11") (pin "P$41") (pinfunction "OSC1_P$41") (pintype "bidirectional"))
    )
    (net (code "58") (name "Net-(U$11-XOSC1)") (class "Default")
      (node (ref "C42") (pin "2") (pinfunction "2_2") (pintype "passive"))
      (node (ref "U$11") (pin "P$36") (pinfunction "XOSC1_P$36") (pintype "bidirectional"))
      (node (ref "U$12") (pin "P$2") (pinfunction "P$2_P$2") (pintype "bidirectional"))
    )
    (net (code "59") (name "Net-(U$11-XOSCO)") (class "Default")
      (node (ref "C41") (pin "1") (pinfunction "1_1") (pintype "passive"))
      (node (ref "U$11") (pin "P$34") (pinfunction "XOSCO_P$34") (pintype "bidirectional"))
      (node (ref "U$12") (pin "P$1") (pinfunction "P$1_P$1") (pintype "bidirectional"))
    )
    (net (code "60") (name "Net-(U$11-~{RST})") (class "Default")
      (node (ref "C30") (pin "2") (pinfunction "2_2") (pintype "passive"))
      (node (ref "R17") (pin "1") (pinfunction "1_1") (pintype "passive"))
      (node (ref "U$11") (pin "P$38") (pinfunction "~{RST}_P$38") (pintype "bidirectional"))
    )
    (net (code "61") (name "Net-(U$11-~{WAKE})") (class "Default")
      (node (ref "R15") (pin "1") (pinfunction "1_1") (pintype "passive"))
      (node (ref "U$11") (pin "P$32") (pinfunction "~{WAKE}_P$32") (pintype "bidirectional"))
    )
    (net (code "62") (name "Net-(U$17-C1_XM)") (class "Default")
      (node (ref "C48") (pin "1") (pinfunction "1_1") (pintype "passive"))
      (node (ref "U$17") (pin "P$7") (pinfunction "C1_XM_P$7") (pintype "bidirectional"))
    )
    (net (code "63") (name "Net-(U$17-SETC_XM)") (class "Default")
      (node (ref "C49") (pin "2") (pinfunction "2_2") (pintype "passive"))
      (node (ref "U$17") (pin "P$8") (pinfunction "SETC_XM_P$8") (pintype "bidirectional"))
    )
    (net (code "64") (name "Net-(U$17-SETP_XM)") (class "Default")
      (node (ref "C49") (pin "1") (pinfunction "1_1") (pintype "passive"))
      (node (ref "U$17") (pin "P$9") (pinfunction "SETP_XM_P$9") (pintype "bidirectional"))
    )
    (net (code "65") (name "SCL-0") (class "Default")
      (node (ref "R1") (pin "1") (pinfunction "1_1") (pintype "passive"))
      (node (ref "TP6") (pin "P$1") (pinfunction "P$1_P$1") (pintype "bidirectional"))
      (node (ref "U$1") (pin "P$7") (pinfunction "SCL_P$7") (pintype "bidirectional"))
      (node (ref "U$11") (pin "P$23") (pinfunction "PA6_P$23") (pintype "bidirectional"))
      (node (ref "U$5") (pin "P$8") (pinfunction "SCL_P$8") (pintype "bidirectional"))
    )
    (net (code "66") (name "SCLK-A") (class "Default")
      (node (ref "U$11") (pin "P$30") (pinfunction "PF2_P$30") (pintype "bidirectional"))
      (node (ref "U$14") (pin "P$6") (pinfunction "A5_P$6") (pintype "bidirectional"))
    )
    (net (code "67") (name "SCLK-B") (class "Default")
      (node (ref "R3") (pin "1") (pinfunction "1_1") (pintype "passive"))
      (node (ref "U$10") (pin "P$4") (pinfunction "SCLK_P$4") (pintype "bidirectional"))
      (node (ref "U$14") (pin "P$15") (pinfunction "B5_P$15") (pintype "bidirectional"))
      (node (ref "U$17") (pin "P$21") (pinfunction "SCL_P$21") (pintype "bidirectional"))
      (node (ref "U$19") (pin "P$4") (pinfunction "SCLK_P$4") (pintype "bidirectional"))
      (node (ref "U$3") (pin "P$2") (pinfunction "SCL_P$2") (pintype "bidirectional"))
      (node (ref "U$4") (pin "P$4") (pinfunction "SCL_P$4") (pintype "bidirectional"))
      (node (ref "U$6") (pin "P$4") (pinfunction "SCL_P$4") (pintype "bidirectional"))
      (node (ref "U$7") (pin "P$1") (pinfunction "SCLK_P$1") (pintype "bidirectional"))
      (node (ref "U$9") (pin "P$4") (pinfunction "SCL_P$4") (pintype "bidirectional"))
    )
    (net (code "68") (name "SD-CARD-INSERT") (class "Default")
      (node (ref "U$11") (pin "P$60") (pinfunction "PE5_P$60") (pintype "bidirectional"))
      (node (ref "U$18") (pin "P$8") (pinfunction "SWITCH2_P$8") (pintype "bidirectional"))
    )
    (net (code "69") (name "SD-CS") (class "Default")
      (node (ref "U$11") (pin "P$62") (pinfunction "PD1_P$62") (pintype "bidirectional"))
      (node (ref "U$18") (pin "P$2") (pinfunction "CS_P$2") (pintype "bidirectional"))
    )
    (net (code "70") (name "SD-MISO") (class "Default")
      (node (ref "U$11") (pin "P$63") (pinfunction "PD2_P$63") (pintype "bidirectional"))
      (node (ref "U$18") (pin "P$7") (pinfunction "D0_P$7") (pintype "bidirectional"))
    )
    (net (code "71") (name "SD-MOSI") (class "Default")
      (node (ref "U$11") (pin "P$64") (pinfunction "PD3_P$64") (pintype "bidirectional"))
      (node (ref "U$18") (pin "P$3") (pinfunction "DI_P$3") (pintype "bidirectional"))
    )
    (net (code "72") (name "SD-SCLK") (class "Default")
      (node (ref "U$11") (pin "P$61") (pinfunction "PD0_P$61") (pintype "bidirectional"))
      (node (ref "U$18") (pin "P$5") (pinfunction "SCLK_P$5") (pintype "bidirectional"))
    )
    (net (code "73") (name "SDA-0") (class "Default")
      (node (ref "R2") (pin "1") (pinfunction "1_1") (pintype "passive"))
      (node (ref "TP5") (pin "P$1") (pinfunction "P$1_P$1") (pintype "bidirectional"))
      (node (ref "U$1") (pin "P$6") (pinfunction "SDA_P$6") (pintype "bidirectional"))
      (node (ref "U$11") (pin "P$24") (pinfunction "PA7_P$24") (pintype "bidirectional"))
      (node (ref "U$5") (pin "P$7") (pinfunction "SDA_P$7") (pintype "bidirectional"))
    )
    (net (code "74") (name "SPI-ADDR0") (class "Default")
      (node (ref "U$11") (pin "P$20") (pinfunction "PA3_P$20") (pintype "bidirectional"))
      (node (ref "U$15") (pin "P$1") (pinfunction "A0_P$1") (pintype "bidirectional"))
    )
    (net (code "75") (name "SPI-ADDR1") (class "Default")
      (node (ref "U$11") (pin "P$19") (pinfunction "PA2_P$19") (pintype "bidirectional"))
      (node (ref "U$15") (pin "P$2") (pinfunction "A1_P$2") (pintype "bidirectional"))
    )
    (net (code "76") (name "SPI-ADDR2") (class "Default")
      (node (ref "U$11") (pin "P$18") (pinfunction "PA1_P$18") (pintype "bidirectional"))
      (node (ref "U$15") (pin "P$3") (pinfunction "A2_P$3") (pintype "bidirectional"))
    )
    (net (code "77") (name "SPI-ENABLE") (class "Default")
      (node (ref "U$11") (pin "P$31") (pinfunction "PF3_P$31") (pintype "bidirectional"))
      (node (ref "U$14") (pin "P$10") (pinfunction "OE_P$10") (pintype "bidirectional"))
    )
    (net (code "78") (name "SWCLK") (class "Default")
      (node (ref "U$11") (pin "P$52") (pinfunction "PC0_P$52") (pintype "bidirectional"))
      (node (ref "X3") (pin "4") (pinfunction "S_4") (pintype "passive"))
    )
    (net (code "79") (name "SWDIO") (class "Default")
      (node (ref "U$11") (pin "P$51") (pinfunction "PC1_P$51") (pintype "bidirectional"))
      (node (ref "X3") (pin "3") (pinfunction "S_3") (pintype "passive"))
    )
    (net (code "80") (name "SWO") (class "Default")
      (node (ref "U$11") (pin "P$49") (pinfunction "PC3_P$49") (pintype "bidirectional"))
      (node (ref "X3") (pin "1") (pinfunction "S_1") (pintype "passive"))
    )
    (net (code "81") (name "TDI") (class "Default")
      (node (ref "U$11") (pin "P$50") (pinfunction "PC2_P$50") (pintype "bidirectional"))
      (node (ref "X3") (pin "2") (pinfunction "S_2") (pintype "passive"))
    )
    (net (code "82") (name "U1RX") (class "Default")
      (node (ref "TP8") (pin "P$1") (pinfunction "P$1_P$1") (pintype "bidirectional"))
      (node (ref "U$11") (pin "P$45") (pinfunction "PB0_P$45") (pintype "bidirectional"))
    )
    (net (code "83") (name "U1TX") (class "Default")
      (node (ref "TP7") (pin "P$1") (pinfunction "P$1_P$1") (pintype "bidirectional"))
      (node (ref "U$11") (pin "P$46") (pinfunction "PB1_P$46") (pintype "bidirectional"))
    )
    (net (code "84") (name "unconnected-(S1-S-Pad3)") (class "Default")
      (node (ref "S1") (pin "3") (pinfunction "S_3") (pintype "passive"))
    )
    (net (code "85") (name "unconnected-(U$1-NC-PadP$3)") (class "Default")
      (node (ref "U$1") (pin "P$3") (pinfunction "NC_P$3") (pintype "bidirectional"))
    )
    (net (code "86") (name "unconnected-(U$3-INT2-PadP$6)") (class "Default")
      (node (ref "U$3") (pin "P$6") (pinfunction "INT2_P$6") (pintype "bidirectional"))
    )
    (net (code "87") (name "unconnected-(U$4-NC$0-PadP$2)") (class "Default")
      (node (ref "U$4") (pin "P$2") (pinfunction "NC$0_P$2") (pintype "bidirectional"))
    )
    (net (code "88") (name "unconnected-(U$4-NC$1-PadP$3)") (class "Default")
      (node (ref "U$4") (pin "P$3") (pinfunction "NC$1_P$3") (pintype "bidirectional"))
    )
    (net (code "89") (name "unconnected-(U$5-INT2-PadP$5)") (class "Default")
      (node (ref "U$5") (pin "P$5") (pinfunction "INT2_P$5") (pintype "bidirectional"))
    )
    (net (code "90") (name "unconnected-(U$6-INT1-PadP$11)") (class "Default")
      (node (ref "U$6") (pin "P$11") (pinfunction "INT1_P$11") (pintype "bidirectional"))
    )
    (net (code "91") (name "unconnected-(U$8-NC-PadP$1)") (class "Default")
      (node (ref "U$8") (pin "P$1") (pinfunction "NC_P$1") (pintype "bidirectional"))
    )
    (net (code "92") (name "unconnected-(U$9-ADC1-PadP$16)") (class "Default")
      (node (ref "U$9") (pin "P$16") (pinfunction "ADC1_P$16") (pintype "bidirectional"))
    )
    (net (code "93") (name "unconnected-(U$9-ADC2-PadP$15)") (class "Default")
      (node (ref "U$9") (pin "P$15") (pinfunction "ADC2_P$15") (pintype "bidirectional"))
    )
    (net (code "94") (name "unconnected-(U$9-ADC3-PadP$13)") (class "Default")
      (node (ref "U$9") (pin "P$13") (pinfunction "ADC3_P$13") (pintype "bidirectional"))
    )
    (net (code "95") (name "unconnected-(U$9-INT1-PadP$11)") (class "Default")
      (node (ref "U$9") (pin "P$11") (pinfunction "INT1_P$11") (pintype "bidirectional"))
    )
    (net (code "96") (name "unconnected-(U$9-NC$0-PadP$2)") (class "Default")
      (node (ref "U$9") (pin "P$2") (pinfunction "NC$0_P$2") (pintype "bidirectional"))
    )
    (net (code "97") (name "unconnected-(U$9-NC$1-PadP$3)") (class "Default")
      (node (ref "U$9") (pin "P$3") (pinfunction "NC$1_P$3") (pintype "bidirectional"))
    )
    (net (code "98") (name "unconnected-(U$10-NC$0-PadP$2)") (class "Default")
      (node (ref "U$10") (pin "P$2") (pinfunction "NC$0_P$2") (pintype "bidirectional"))
    )
    (net (code "99") (name "unconnected-(U$10-NC$1-PadP$15)") (class "Default")
      (node (ref "U$10") (pin "P$15") (pinfunction "NC$1_P$15") (pintype "bidirectional"))
    )
    (net (code "100") (name "unconnected-(U$10-RSVD$0-PadP$3)") (class "Default")
      (node (ref "U$10") (pin "P$3") (pinfunction "RSVD$0_P$3") (pintype "bidirectional"))
    )
    (net (code "101") (name "unconnected-(U$10-RSVD$1-PadP$5)") (class "Default")
      (node (ref "U$10") (pin "P$5") (pinfunction "RSVD$1_P$5") (pintype "bidirectional"))
    )
    (net (code "102") (name "unconnected-(U$10-RSVD$2-PadP$10)") (class "Default")
      (node (ref "U$10") (pin "P$10") (pinfunction "RSVD$2_P$10") (pintype "bidirectional"))
    )
    (net (code "103") (name "unconnected-(U$11-PA4-PadP$21)") (class "Default")
      (node (ref "U$11") (pin "P$21") (pinfunction "PA4_P$21") (pintype "bidirectional"))
    )
    (net (code "104") (name "unconnected-(U$11-PA5-PadP$22)") (class "Default")
      (node (ref "U$11") (pin "P$22") (pinfunction "PA5_P$22") (pintype "bidirectional"))
    )
    (net (code "105") (name "unconnected-(U$11-PB2-PadP$47)") (class "Default")
      (node (ref "U$11") (pin "P$47") (pinfunction "PB2_P$47") (pintype "bidirectional"))
    )
    (net (code "106") (name "unconnected-(U$11-PB4-PadP$58)") (class "Default")
      (node (ref "U$11") (pin "P$58") (pinfunction "PB4_P$58") (pintype "bidirectional"))
    )
    (net (code "107") (name "unconnected-(U$11-PB5-PadP$57)") (class "Default")
      (node (ref "U$11") (pin "P$57") (pinfunction "PB5_P$57") (pintype "bidirectional"))
    )
    (net (code "108") (name "unconnected-(U$11-PD5-PadP$44)") (class "Default")
      (node (ref "U$11") (pin "P$44") (pinfunction "PD5_P$44") (pintype "bidirectional"))
    )
    (net (code "109") (name "unconnected-(U$11-PD6-PadP$53)") (class "Default")
      (node (ref "U$11") (pin "P$53") (pinfunction "PD6_P$53") (pintype "bidirectional"))
    )
    (net (code "110") (name "unconnected-(U$11-PD7-PadP$10)") (class "Default")
      (node (ref "U$11") (pin "P$10") (pinfunction "PD7_P$10") (pintype "bidirectional"))
    )
    (net (code "111") (name "unconnected-(U$11-PE4-PadP$59)") (class "Default")
      (node (ref "U$11") (pin "P$59") (pinfunction "PE4_P$59") (pintype "bidirectional"))
    )
    (net (code "112") (name "unconnected-(U$11-~{HIB}-PadP$33)") (class "Default")
      (node (ref "U$11") (pin "P$33") (pinfunction "~{HIB}_P$33") (pintype "bidirectional"))
    )
    (net (code "113") (name "unconnected-(U$14-A1-PadP$1)") (class "Default")
      (node (ref "U$14") (pin "P$1") (pinfunction "A1_P$1") (pintype "bidirectional"))
    )
    (net (code "114") (name "unconnected-(U$14-A2-PadP$3)") (class "Default")
      (node (ref "U$14") (pin "P$3") (pinfunction "A2_P$3") (pintype "bidirectional"))
    )
    (net (code "115") (name "unconnected-(U$14-A3-PadP$4)") (class "Default")
      (node (ref "U$14") (pin "P$4") (pinfunction "A3_P$4") (pintype "bidirectional"))
    )
    (net (code "116") (name "unconnected-(U$14-A4-PadP$5)") (class "Default")
      (node (ref "U$14") (pin "P$5") (pinfunction "A4_P$5") (pintype "bidirectional"))
    )
    (net (code "117") (name "unconnected-(U$14-A6-PadP$7)") (class "Default")
      (node (ref "U$14") (pin "P$7") (pinfunction "A6_P$7") (pintype "bidirectional"))
    )
    (net (code "118") (name "unconnected-(U$14-A8-PadP$9)") (class "Default")
      (node (ref "U$14") (pin "P$9") (pinfunction "A8_P$9") (pintype "bidirectional"))
    )
    (net (code "119") (name "unconnected-(U$14-B1-PadP$20)") (class "Default")
      (node (ref "U$14") (pin "P$20") (pinfunction "B1_P$20") (pintype "bidirectional"))
    )
    (net (code "120") (name "unconnected-(U$14-B2-PadP$18)") (class "Default")
      (node (ref "U$14") (pin "P$18") (pinfunction "B2_P$18") (pintype "bidirectional"))
    )
    (net (code "121") (name "unconnected-(U$14-B3-PadP$17)") (class "Default")
      (node (ref "U$14") (pin "P$17") (pinfunction "B3_P$17") (pintype "bidirectional"))
    )
    (net (code "122") (name "unconnected-(U$14-B4-PadP$16)") (class "Default")
      (node (ref "U$14") (pin "P$16") (pinfunction "B4_P$16") (pintype "bidirectional"))
    )
    (net (code "123") (name "unconnected-(U$14-B8-PadP$12)") (class "Default")
      (node (ref "U$14") (pin "P$12") (pinfunction "B8_P$12") (pintype "bidirectional"))
    )
    (net (code "124") (name "unconnected-(U$16-NC#0-PadP$1)") (class "Default")
      (node (ref "U$16") (pin "P$1") (pinfunction "NC#0_P$1") (pintype "bidirectional"))
    )
    (net (code "125") (name "unconnected-(U$16-NC#1-PadP$2)") (class "Default")
      (node (ref "U$16") (pin "P$2") (pinfunction "NC#1_P$2") (pintype "bidirectional"))
    )
    (net (code "126") (name "unconnected-(U$16-NC#2-PadP$5)") (class "Default")
      (node (ref "U$16") (pin "P$5") (pinfunction "NC#2_P$5") (pintype "bidirectional"))
    )
    (net (code "127") (name "unconnected-(U$17-INT2_XM-PadP$14)") (class "Default")
      (node (ref "U$17") (pin "P$14") (pinfunction "INT2_XM_P$14") (pintype "bidirectional"))
    )
    (net (code "128") (name "unconnected-(U$17-RES#0-PadP$1)") (class "Default")
      (node (ref "U$17") (pin "P$1") (pinfunction "RES#0_P$1") (pintype "bidirectional"))
    )
    (net (code "129") (name "unconnected-(U$18-GND#1-PadP$10)") (class "Default")
      (node (ref "U$18") (pin "P$10") (pinfunction "GND#1_P$10") (pintype "bidirectional"))
    )
    (net (code "130") (name "unconnected-(U$18-GND#2-PadP$11)") (class "Default")
      (node (ref "U$18") (pin "P$11") (pinfunction "GND#2_P$11") (pintype "bidirectional"))
    )
    (net (code "131") (name "unconnected-(U$18-GND#3-PadP$12)") (class "Default")
      (node (ref "U$18") (pin "P$12") (pinfunction "GND#3_P$12") (pintype "bidirectional"))
    )
    (net (code "132") (name "unconnected-(U$18-GND#4-PadP$13)") (class "Default")
      (node (ref "U$18") (pin "P$13") (pinfunction "GND#4_P$13") (pintype "bidirectional"))
    )
    (net (code "133") (name "unconnected-(U$18-RSV-PadP$1)") (class "Default")
      (node (ref "U$18") (pin "P$1") (pinfunction "RSV_P$1") (pintype "bidirectional"))
    )
    (net (code "134") (name "unconnected-(U$19-DSYNC-PadP$12)") (class "Default")
      (node (ref "U$19") (pin "P$12") (pinfunction "DSYNC_P$12") (pintype "bidirectional"))
    )
    (net (code "135") (name "unconnected-(U$19-INT1-PadP$11)") (class "Default")
      (node (ref "U$19") (pin "P$11") (pinfunction "INT1_P$11") (pintype "bidirectional"))
    )
    (net (code "136") (name "unconnected-(U$19-NC#0-PadP$2)") (class "Default")
      (node (ref "U$19") (pin "P$2") (pinfunction "NC#0_P$2") (pintype "bidirectional"))
    )
    (net (code "137") (name "unconnected-(U$19-NC#1-PadP$3)") (class "Default")
      (node (ref "U$19") (pin "P$3") (pinfunction "NC#1_P$3") (pintype "bidirectional"))
    )
    (net (code "138") (name "unconnected-(U$19-NC#2-PadP$16)") (class "Default")
      (node (ref "U$19") (pin "P$16") (pinfunction "NC#2_P$16") (pintype "bidirectional"))
    )
    (net (code "139") (name "unconnected-(U$19-RSVD#0-PadP$10)") (class "Default")
      (node (ref "U$19") (pin "P$10") (pinfunction "RSVD#0_P$10") (pintype "bidirectional"))
    )
    (net (code "140") (name "unconnected-(U$19-RSVD#1-PadP$13)") (class "Default")
      (node (ref "U$19") (pin "P$13") (pinfunction "RSVD#1_P$13") (pintype "bidirectional"))
    )
    (net (code "141") (name "unconnected-(U$19-VDDIO-PadP$1)") (class "Default")
      (node (ref "U$19") (pin "P$1") (pinfunction "VDDIO_P$1") (pintype "bidirectional"))
    )
  )
)
